# VTL_Sensor_System.net
KiCad netlist of a schematic drawn in Altium Designer
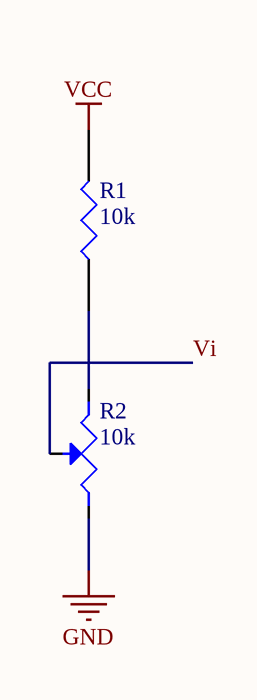
[diagram p0: VTL Sensor System.SchDoc]

(export (version "E")
  (design (tool "Eeschema 10.0.6"))
  (components
    (comp (ref "R1")
      (value "10k")
      (footprint "AXIAL-0.4")
      (libsource (lib "Miscellaneous Devices") (part "RES1"))
    )
    (comp (ref "R2")
      (value "10k")
      (footprint "VR-5")
      (description "Potentiometer")
      (libsource (lib "Miscellaneous Devices") (part "POT1"))
    )
  )
  (nets
    (net (code "1") (name "/Vi") (class "Default")
      (node (ref "R2") (pin "3") (pinfunction "W_3") (pintype "passive"))
    )
    (net (code "2") (name "GND") (class "Default")
      (node (ref "R2") (pin "1") (pinfunction "1_1") (pintype "passive"))
    )
    (net (code "3") (name "Net-(R1-Pad1)") (class "Default")
      (node (ref "R1") (pin "1") (pinfunction "1_1") (pintype "passive"))
      (node (ref "R2") (pin "2") (pinfunction "2_2") (pintype "passive"))
    )
    (net (code "4") (name "VCC") (class "Default")
      (node (ref "R1") (pin "2") (pinfunction "2_2") (pintype "passive"))
    )
  )
)
